# USB3300.net
KiCad netlist of a schematic drawn in Altium Designer
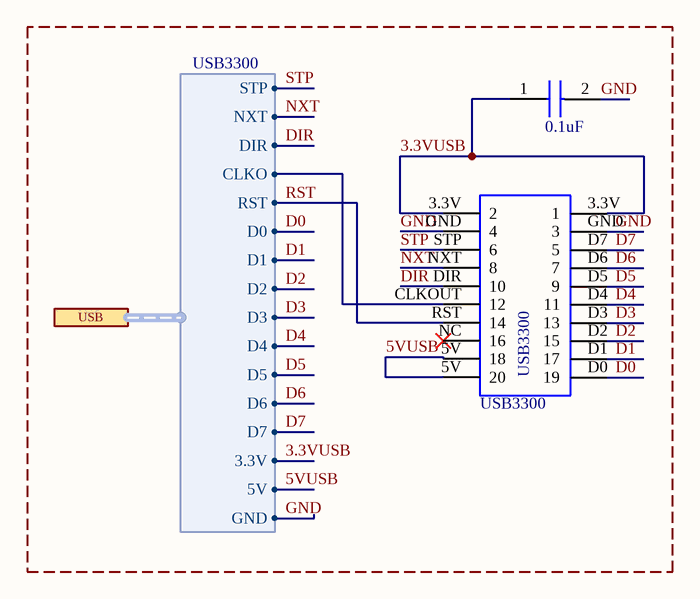
[diagram p0: USB3300.SchDoc]

(export (version "E")
  (design (tool "Eeschema 10.0.6"))
  (components
    (comp (ref "CAPUSB3V")
      (value "0.1uF")
      (footprint "CAP0805")
      (description "CAP-SMD0805")
      (libsource (lib "Components_Robots") (part "CAP0805"))
    )
    (comp (ref "USB3300")
      (value "USB3300")
      (footprint "USB3300")
      (description "USB3300HS")
      (libsource (lib "Components_Robots") (part "USB3300"))
    )
  )
  (nets
    (net (code "2") (name "/3.3VUSB") (class "Default")
      (node (ref "CAPUSB3V") (pin "1") (pinfunction "1_1") (pintype "passive"))
      (node (ref "USB3300") (pin "3.3V") (pinfunction "2_3.3V") (pintype "passive"))
    )
    (net (code "3") (name "/5VUSB") (class "Default")
      (node (ref "USB3300") (pin "5V") (pinfunction "18_5V") (pintype "passive"))
    )
    (net (code "4") (name "/CLKO") (class "Default")
      (node (ref "USB3300") (pin "CLKOUT") (pinfunction "12_CLKOUT") (pintype "passive"))
    )
    (net (code "5") (name "/D0") (class "Default")
      (node (ref "USB3300") (pin "D0") (pinfunction "19_D0") (pintype "passive"))
    )
    (net (code "6") (name "/D1") (class "Default")
      (node (ref "USB3300") (pin "D1") (pinfunction "17_D1") (pintype "passive"))
    )
    (net (code "7") (name "/D2") (class "Default")
      (node (ref "USB3300") (pin "D2") (pinfunction "15_D2") (pintype "passive"))
    )
    (net (code "8") (name "/D3") (class "Default")
      (node (ref "USB3300") (pin "D3") (pinfunction "13_D3") (pintype "passive"))
    )
    (net (code "9") (name "/D4") (class "Default")
      (node (ref "USB3300") (pin "D4") (pinfunction "11_D4") (pintype "passive"))
    )
    (net (code "10") (name "/D5") (class "Default")
      (node (ref "USB3300") (pin "D5") (pinfunction "9_D5") (pintype "passive"))
    )
    (net (code "11") (name "/D6") (class "Default")
      (node (ref "USB3300") (pin "D6") (pinfunction "7_D6") (pintype "passive"))
    )
    (net (code "12") (name "/D7") (class "Default")
      (node (ref "USB3300") (pin "D7") (pinfunction "5_D7") (pintype "passive"))
    )
    (net (code "13") (name "/DIR") (class "Default")
      (node (ref "USB3300") (pin "DIR") (pinfunction "10_DIR") (pintype "passive"))
    )
    (net (code "14") (name "/GND") (class "Default")
      (node (ref "CAPUSB3V") (pin "2") (pinfunction "2_2") (pintype "passive"))
      (node (ref "USB3300") (pin "GND") (pinfunction "4_GND") (pintype "passive"))
    )
    (net (code "15") (name "/NXT") (class "Default")
      (node (ref "USB3300") (pin "NXT") (pinfunction "8_NXT") (pintype "passive"))
    )
    (net (code "16") (name "/RST") (class "Default")
      (node (ref "USB3300") (pin "RST") (pinfunction "14_RST") (pintype "passive"))
    )
    (net (code "17") (name "/STP") (class "Default")
      (node (ref "USB3300") (pin "STP") (pinfunction "6_STP") (pintype "passive"))
    )
    (net (code "19") (name "unconnected-(USB3300-16-PadNC)") (class "Default")
      (node (ref "USB3300") (pin "NC") (pinfunction "16_NC") (pintype "passive+no_connect"))
    )
  )
)
